# Cool_White_LEDs.net
KiCad netlist of a schematic drawn in Altium Designer
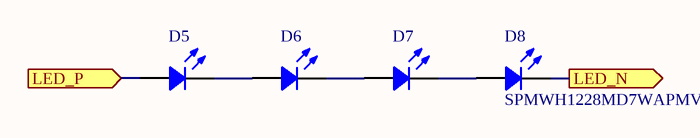
[diagram p0: Cool White LEDs.SchDoc]

(export (version "E")
  (design (tool "Eeschema 10.0.6"))
  (components
    (comp (ref "D5")
      (value "SPMWH1228MD7WAPMVL")
      (footprint "SAMSUNG LM281BPLUS")
      (description "LED")
      (fields (field (name "MANUFACTURER") "Samsung Semiconductor, Inc."))
      (libsource (lib "altiumlibrary.com") (part "LED A-C"))
    )
    (comp (ref "D6")
      (value "SPMWH1228MD7WAPMVL")
      (footprint "SAMSUNG LM281BPLUS")
      (description "LED")
      (fields (field (name "MANUFACTURER") "Samsung Semiconductor, Inc."))
      (libsource (lib "altiumlibrary.com") (part "LED A-C"))
    )
    (comp (ref "D7")
      (value "SPMWH1228MD7WAPMVL")
      (footprint "SAMSUNG LM281BPLUS")
      (description "LED")
      (fields (field (name "MANUFACTURER") "Samsung Semiconductor, Inc."))
      (libsource (lib "altiumlibrary.com") (part "LED A-C"))
    )
    (comp (ref "D8")
      (value "SPMWH1228MD7WAPMVL")
      (footprint "SAMSUNG LM281BPLUS")
      (description "LED")
      (fields (field (name "MANUFACTURER") "Samsung Semiconductor, Inc."))
      (libsource (lib "altiumlibrary.com") (part "LED A-C"))
    )
  )
  (nets
    (net (code "1") (name "/LED_N") (class "Default")
      (node (ref "D8") (pin "C") (pinfunction "C_C") (pintype "passive"))
    )
    (net (code "2") (name "/LED_P") (class "Default")
      (node (ref "D5") (pin "A") (pinfunction "A_A") (pintype "passive"))
    )
    (net (code "3") (name "Net-(D5-PadC)") (class "Default")
      (node (ref "D5") (pin "C") (pinfunction "C_C") (pintype "passive"))
      (node (ref "D6") (pin "A") (pinfunction "A_A") (pintype "passive"))
    )
    (net (code "4") (name "Net-(D6-PadC)") (class "Default")
      (node (ref "D6") (pin "C") (pinfunction "C_C") (pintype "passive"))
      (node (ref "D7") (pin "A") (pinfunction "A_A") (pintype "passive"))
    )
    (net (code "5") (name "Net-(D7-PadC)") (class "Default")
      (node (ref "D7") (pin "C") (pinfunction "C_C") (pintype "passive"))
      (node (ref "D8") (pin "A") (pinfunction "A_A") (pintype "passive"))
    )
  )
)
